# VISUB_V1.net
KiCad netlist of a schematic drawn in EAGLE
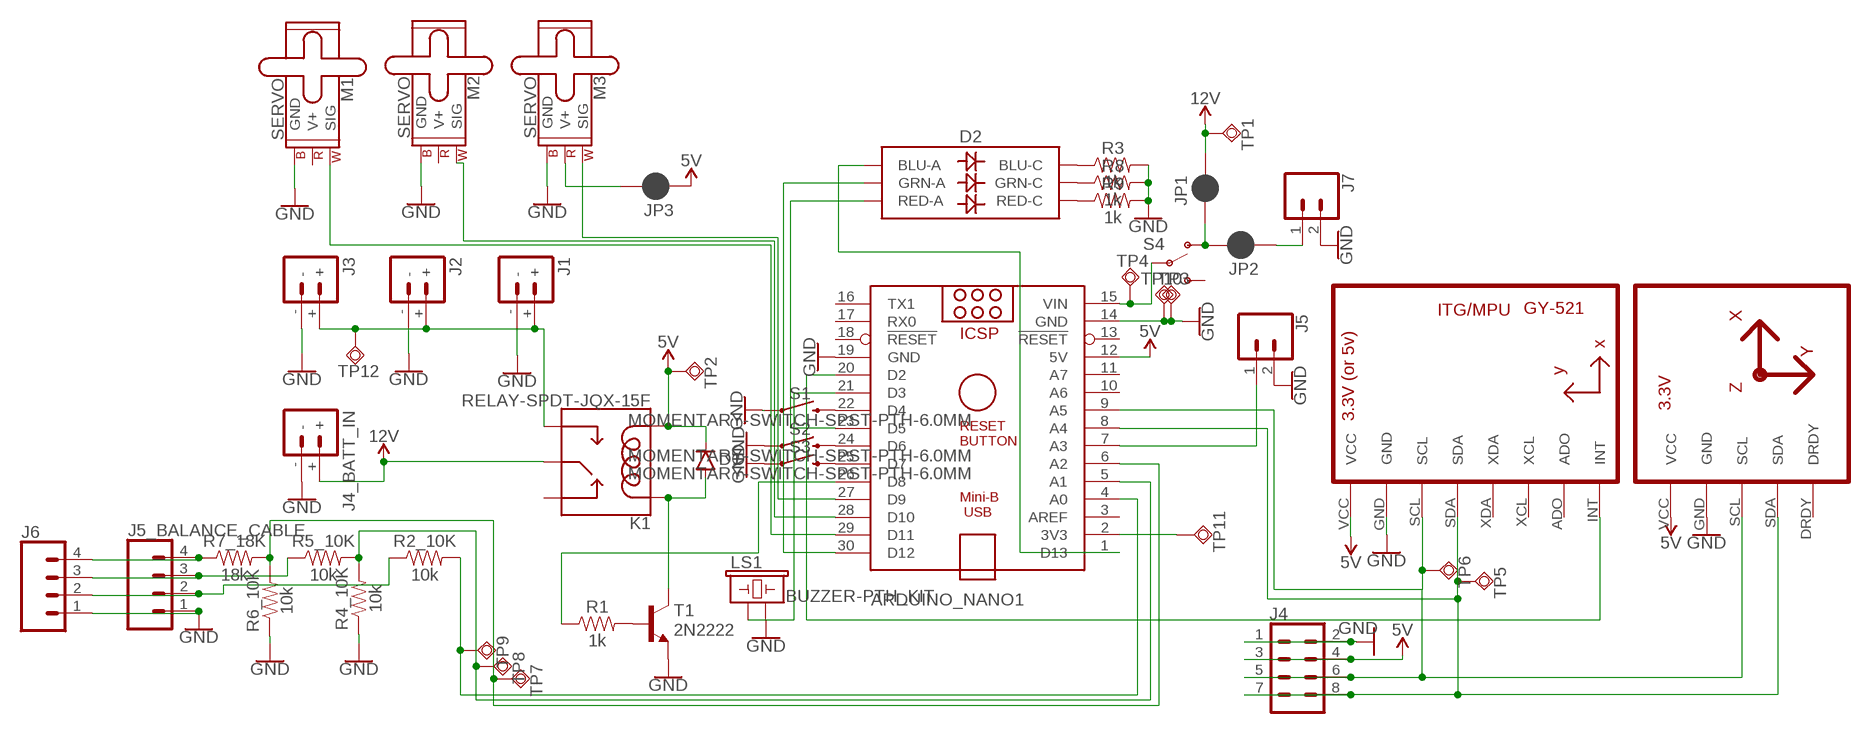
[diagram p0: schematic, sheet 1]

(export (version "E")
  (design (tool "Eeschema 10.0.6"))
  (components
    (comp (ref "ARDUINO_NANO1")
      (value "ARDUINO_NANO")
      (footprint "eagle-import:ARDUINO_NANO")
      (libsource (lib "eagle-import") (part "ARDUINO_NANO"))
    )
    (comp (ref "D1")
      (value "DIODE1N4148")
      (footprint "eagle-import:DIODE-1N4148")
      (libsource (lib "eagle-import") (part "DIODE1N4148"))
    )
    (comp (ref "D2")
      (value "LED-RGBNO_IC")
      (footprint "eagle-import:LED-TRICOLOR-5050")
      (libsource (lib "eagle-import") (part "LED-RGBNO_IC"))
    )
    (comp (ref "J1")
      (value "BATTERY_CONN_DEANS")
      (footprint "eagle-import:DEANS")
      (libsource (lib "eagle-import") (part "BATTERY_CONN_DEANS"))
    )
    (comp (ref "J2")
      (value "BATTERY_CONN_DEANS")
      (footprint "eagle-import:DEANS")
      (libsource (lib "eagle-import") (part "BATTERY_CONN_DEANS"))
    )
    (comp (ref "J3")
      (value "BATTERY_CONN_DEANS")
      (footprint "eagle-import:DEANS")
      (libsource (lib "eagle-import") (part "BATTERY_CONN_DEANS"))
    )
    (comp (ref "J4")
      (value "CONN_04X2")
      (footprint "eagle-import:2X4")
      (libsource (lib "eagle-import") (part "CONN_04X2"))
    )
    (comp (ref "J4_BATT_IN")
      (value "BATTERY_CONN_DEANS")
      (footprint "eagle-import:DEANS")
      (libsource (lib "eagle-import") (part "BATTERY_CONN_DEANS"))
    )
    (comp (ref "J5")
      (value "CONN_02")
      (footprint "eagle-import:1X02")
      (libsource (lib "eagle-import") (part "CONN_02"))
    )
    (comp (ref "J5_BALANCE_CABLE")
      (value "CONN_04POLAR")
      (footprint "eagle-import:MOLEX-1X4")
      (libsource (lib "eagle-import") (part "CONN_04POLAR"))
    )
    (comp (ref "J6")
      (value "CONN_04POLAR")
      (footprint "eagle-import:MOLEX-1X4")
      (libsource (lib "eagle-import") (part "CONN_04POLAR"))
    )
    (comp (ref "J7")
      (value "CONN_02")
      (footprint "eagle-import:1X02")
      (libsource (lib "eagle-import") (part "CONN_02"))
    )
    (comp (ref "JP1")
      (value "JUMPER-SMT_2_NC_PASTE_SILK")
      (footprint "eagle-import:SMT-JUMPER_2_NC_PASTE_SILK")
      (libsource (lib "eagle-import") (part "JUMPER-SMT_2_NC_PASTE_SILK"))
    )
    (comp (ref "JP2")
      (value "JUMPER-SMT_2_NC_PASTE_SILK")
      (footprint "eagle-import:SMT-JUMPER_2_NC_PASTE_SILK")
      (libsource (lib "eagle-import") (part "JUMPER-SMT_2_NC_PASTE_SILK"))
    )
    (comp (ref "JP3")
      (value "JUMPER-SMT_2_NC_PASTE_SILK")
      (footprint "eagle-import:SMT-JUMPER_2_NC_PASTE_SILK")
      (libsource (lib "eagle-import") (part "JUMPER-SMT_2_NC_PASTE_SILK"))
    )
    (comp (ref "K1")
      (value "RELAY-SPDT-JQX-15F")
      (footprint "eagle-import:RELAY-T90")
      (libsource (lib "eagle-import") (part "RELAY-SPDT-JQX-15F"))
    )
    (comp (ref "LS1")
      (value "BUZZER-PTH_KIT")
      (footprint "eagle-import:BUZZER-12MM-KIT")
      (libsource (lib "eagle-import") (part "BUZZER-PTH_KIT"))
    )
    (comp (ref "M1")
      (value "SERVO")
      (footprint "eagle-import:1X03")
      (libsource (lib "eagle-import") (part "SERVO"))
    )
    (comp (ref "M2")
      (value "SERVO")
      (footprint "eagle-import:1X03")
      (libsource (lib "eagle-import") (part "SERVO"))
    )
    (comp (ref "M3")
      (value "SERVO")
      (footprint "eagle-import:1X03")
      (libsource (lib "eagle-import") (part "SERVO"))
    )
    (comp (ref "R1")
      (value "1k")
      (footprint "eagle-import:AXIAL-0.3")
      (libsource (lib "eagle-import") (part "1KOHM-HORIZ-1/4W-5%"))
    )
    (comp (ref "R2_10K")
      (value "10k")
      (footprint "eagle-import:AXIAL-0.3")
      (libsource (lib "eagle-import") (part "1KOHM-HORIZ-1/4W-5%"))
    )
    (comp (ref "R3")
      (value "1k")
      (footprint "eagle-import:0603")
      (libsource (lib "eagle-import") (part "1KOHM-0603-1/10W-1%"))
    )
    (comp (ref "R4_10K")
      (value "10k")
      (footprint "eagle-import:AXIAL-0.3")
      (libsource (lib "eagle-import") (part "1KOHM-HORIZ-1/4W-5%"))
    )
    (comp (ref "R5_10K")
      (value "10k")
      (footprint "eagle-import:AXIAL-0.3")
      (libsource (lib "eagle-import") (part "1KOHM-HORIZ-1/4W-5%"))
    )
    (comp (ref "R6_10K")
      (value "10k")
      (footprint "eagle-import:AXIAL-0.3")
      (libsource (lib "eagle-import") (part "1KOHM-HORIZ-1/4W-5%"))
    )
    (comp (ref "R7_18K")
      (value "18k")
      (footprint "eagle-import:AXIAL-0.3")
      (libsource (lib "eagle-import") (part "1KOHM-HORIZ-1/4W-5%"))
    )
    (comp (ref "R8")
      (value "1k")
      (footprint "eagle-import:0603")
      (libsource (lib "eagle-import") (part "1KOHM-0603-1/10W-1%"))
    )
    (comp (ref "R9")
      (value "1k")
      (footprint "eagle-import:0603")
      (libsource (lib "eagle-import") (part "1KOHM-0603-1/10W-1%"))
    )
    (comp (ref "S1")
      (value "MOMENTARY-SWITCH-SPST-PTH-6.0MM")
      (footprint "eagle-import:TACTILE_SWITCH_PTH_6.0MM")
      (libsource (lib "eagle-import") (part "MOMENTARY-SWITCH-SPST-PTH-6.0MM"))
    )
    (comp (ref "S2")
      (value "MOMENTARY-SWITCH-SPST-PTH-6.0MM")
      (footprint "eagle-import:TACTILE_SWITCH_PTH_6.0MM")
      (libsource (lib "eagle-import") (part "MOMENTARY-SWITCH-SPST-PTH-6.0MM"))
    )
    (comp (ref "S3")
      (value "MOMENTARY-SWITCH-SPST-PTH-6.0MM")
      (footprint "eagle-import:TACTILE_SWITCH_PTH_6.0MM")
      (libsource (lib "eagle-import") (part "MOMENTARY-SWITCH-SPST-PTH-6.0MM"))
    )
    (comp (ref "S4")
      (value "SWITCH-SPDT-PTH-11.6X4.0MM-LOCK")
      (footprint "eagle-import:SWITCH_SPDT_PTH_11.6X4.0MM_LOCK")
      (libsource (lib "eagle-import") (part "SWITCH-SPDT-PTH-11.6X4.0MM-LOCK"))
    )
    (comp (ref "T1")
      (value "2N2222")
      (footprint "eagle-import:TO92-EBC-OVAL")
      (libsource (lib "eagle-import") (part "2N2222"))
    )
    (comp (ref "TP1")
      (value "TESTPAD_TPSQB2,54")
      (footprint "eagle-import:TESTPAD_B2,54")
      (libsource (lib "eagle-import") (part "TESTPAD_TPSQB2,54"))
    )
    (comp (ref "TP2")
      (value "TESTPAD_TPSQB2,54")
      (footprint "eagle-import:TESTPAD_B2,54")
      (libsource (lib "eagle-import") (part "TESTPAD_TPSQB2,54"))
    )
    (comp (ref "TP3")
      (value "TESTPAD_TPSQB2,54")
      (footprint "eagle-import:TESTPAD_B2,54")
      (libsource (lib "eagle-import") (part "TESTPAD_TPSQB2,54"))
    )
    (comp (ref "TP4")
      (value "TESTPAD_TPSQB2,54")
      (footprint "eagle-import:TESTPAD_B2,54")
      (libsource (lib "eagle-import") (part "TESTPAD_TPSQB2,54"))
    )
    (comp (ref "TP5")
      (value "TESTPAD_TPSQB2,54")
      (footprint "eagle-import:TESTPAD_B2,54")
      (libsource (lib "eagle-import") (part "TESTPAD_TPSQB2,54"))
    )
    (comp (ref "TP6")
      (value "TESTPAD_TPSQB2,54")
      (footprint "eagle-import:TESTPAD_B2,54")
      (libsource (lib "eagle-import") (part "TESTPAD_TPSQB2,54"))
    )
    (comp (ref "TP7")
      (value "TESTPAD_TPSQB2,54")
      (footprint "eagle-import:TESTPAD_B2,54")
      (libsource (lib "eagle-import") (part "TESTPAD_TPSQB2,54"))
    )
    (comp (ref "TP8")
      (value "TESTPAD_TPSQB2,54")
      (footprint "eagle-import:TESTPAD_B2,54")
      (libsource (lib "eagle-import") (part "TESTPAD_TPSQB2,54"))
    )
    (comp (ref "TP9")
      (value "TESTPAD_TPSQB2,54")
      (footprint "eagle-import:TESTPAD_B2,54")
      (libsource (lib "eagle-import") (part "TESTPAD_TPSQB2,54"))
    )
    (comp (ref "TP10")
      (value "TESTPAD_TPSQB2,54")
      (footprint "eagle-import:TESTPAD_B2,54")
      (libsource (lib "eagle-import") (part "TESTPAD_TPSQB2,54"))
    )
    (comp (ref "TP11")
      (value "TESTPAD_TPSQB2,54")
      (footprint "eagle-import:TESTPAD_B2,54")
      (libsource (lib "eagle-import") (part "TESTPAD_TPSQB2,54"))
    )
    (comp (ref "TP12")
      (value "TESTPAD_TPSQB2,54")
      (footprint "eagle-import:TESTPAD_B2,54")
      (libsource (lib "eagle-import") (part "TESTPAD_TPSQB2,54"))
    )
    (comp (ref "U1")
      (value "GY-521MPU6050")
      (footprint "eagle-import:GY-521")
      (libsource (lib "eagle-import") (part "GY-521MPU6050"))
    )
    (comp (ref "U2")
      (value "HMC5883LGY-271")
      (footprint "eagle-import:GY-271")
      (libsource (lib "eagle-import") (part "HMC5883LGY-271"))
    )
  )
  (nets
    (net (code "1") (name "5V") (class "Default")
      (node (ref "ARDUINO_NANO1") (pin "12") (pinfunction "5V_12") (pintype "power_in"))
      (node (ref "D1") (pin "C") (pinfunction "C_C") (pintype "passive"))
      (node (ref "J4") (pin "3") (pinfunction "3_3") (pintype "passive"))
      (node (ref "J4") (pin "4") (pinfunction "4_4") (pintype "passive"))
      (node (ref "JP3") (pin "1") (pinfunction "1_1") (pintype "passive"))
      (node (ref "K1") (pin "COIL2") (pinfunction "COIL2_COIL2") (pintype "bidirectional"))
      (node (ref "TP2") (pin "TP") (pinfunction "TP_TP") (pintype "input"))
      (node (ref "U1") (pin "VCC") (pinfunction "VCC_VCC") (pintype "bidirectional"))
      (node (ref "U2") (pin "VCC") (pinfunction "VCC_VCC") (pintype "bidirectional"))
    )
    (net (code "2") (name "12V") (class "Default")
      (node (ref "J4_BATT_IN") (pin "+") (pinfunction "+_+") (pintype "passive"))
      (node (ref "JP1") (pin "2") (pinfunction "2_2") (pintype "passive"))
      (node (ref "K1") (pin "MAIN") (pinfunction "MAIN_MAIN") (pintype "bidirectional"))
      (node (ref "TP1") (pin "TP") (pinfunction "TP_TP") (pintype "input"))
    )
    (net (code "3") (name "GND") (class "Default")
      (node (ref "ARDUINO_NANO1") (pin "14") (pinfunction "GND_14") (pintype "power_in"))
      (node (ref "ARDUINO_NANO1") (pin "19") (pinfunction "GND_19") (pintype "power_in"))
      (node (ref "J1") (pin "-") (pinfunction "-_-") (pintype "passive"))
      (node (ref "J2") (pin "-") (pinfunction "-_-") (pintype "passive"))
      (node (ref "J3") (pin "-") (pinfunction "-_-") (pintype "passive"))
      (node (ref "J4") (pin "1") (pinfunction "1_1") (pintype "passive"))
      (node (ref "J4") (pin "2") (pinfunction "2_2") (pintype "passive"))
      (node (ref "J4_BATT_IN") (pin "-") (pinfunction "-_-") (pintype "passive"))
      (node (ref "J5") (pin "2") (pinfunction "2_2") (pintype "passive"))
      (node (ref "J5_BALANCE_CABLE") (pin "1") (pinfunction "1_1") (pintype "passive"))
      (node (ref "J6") (pin "1") (pinfunction "1_1") (pintype "passive"))
      (node (ref "J7") (pin "2") (pinfunction "2_2") (pintype "passive"))
      (node (ref "LS1") (pin "-") (pinfunction "2_-") (pintype "passive"))
      (node (ref "M1") (pin "3") (pinfunction "GND_3") (pintype "bidirectional"))
      (node (ref "M2") (pin "3") (pinfunction "GND_3") (pintype "bidirectional"))
      (node (ref "M3") (pin "3") (pinfunction "GND_3") (pintype "bidirectional"))
      (node (ref "R3") (pin "2") (pinfunction "2_2") (pintype "passive"))
      (node (ref "R4_10K") (pin "P$1") (pinfunction "1_P$1") (pintype "passive"))
      (node (ref "R6_10K") (pin "P$1") (pinfunction "1_P$1") (pintype "passive"))
      (node (ref "R8") (pin "2") (pinfunction "2_2") (pintype "passive"))
      (node (ref "R9") (pin "2") (pinfunction "2_2") (pintype "passive"))
      (node (ref "S1") (pin "1") (pinfunction "1_1") (pintype "passive"))
      (node (ref "S2") (pin "1") (pinfunction "1_1") (pintype "passive"))
      (node (ref "S3") (pin "1") (pinfunction "1_1") (pintype "passive"))
      (node (ref "T1") (pin "E") (pinfunction "E_E") (pintype "passive"))
      (node (ref "TP10") (pin "TP") (pinfunction "TP_TP") (pintype "input"))
      (node (ref "TP3") (pin "TP") (pinfunction "TP_TP") (pintype "input"))
      (node (ref "U1") (pin "GND") (pinfunction "GND_GND") (pintype "bidirectional"))
      (node (ref "U2") (pin "GND") (pinfunction "GND_GND") (pintype "bidirectional"))
    )
    (net (code "4") (name "Net-(ARDUINO_NANO1-3V3)") (class "Default")
      (node (ref "ARDUINO_NANO1") (pin "2") (pinfunction "3V3_2") (pintype "output"))
      (node (ref "TP11") (pin "TP") (pinfunction "TP_TP") (pintype "input"))
    )
    (net (code "5") (name "Net-(ARDUINO_NANO1-A0)") (class "Default")
      (node (ref "ARDUINO_NANO1") (pin "4") (pinfunction "A0_4") (pintype "bidirectional"))
      (node (ref "R2_10K") (pin "P$2") (pinfunction "2_P$2") (pintype "passive"))
      (node (ref "TP9") (pin "TP") (pinfunction "TP_TP") (pintype "input"))
    )
    (net (code "6") (name "Net-(ARDUINO_NANO1-A1)") (class "Default")
      (node (ref "ARDUINO_NANO1") (pin "5") (pinfunction "A1_5") (pintype "bidirectional"))
      (node (ref "R4_10K") (pin "P$2") (pinfunction "2_P$2") (pintype "passive"))
      (node (ref "R5_10K") (pin "P$2") (pinfunction "2_P$2") (pintype "passive"))
      (node (ref "TP8") (pin "TP") (pinfunction "TP_TP") (pintype "input"))
    )
    (net (code "7") (name "Net-(ARDUINO_NANO1-A2)") (class "Default")
      (node (ref "ARDUINO_NANO1") (pin "6") (pinfunction "A2_6") (pintype "bidirectional"))
      (node (ref "R6_10K") (pin "P$2") (pinfunction "2_P$2") (pintype "passive"))
      (node (ref "R7_18K") (pin "P$2") (pinfunction "2_P$2") (pintype "passive"))
      (node (ref "TP7") (pin "TP") (pinfunction "TP_TP") (pintype "input"))
    )
    (net (code "8") (name "Net-(ARDUINO_NANO1-A3)") (class "Default")
      (node (ref "ARDUINO_NANO1") (pin "7") (pinfunction "A3_7") (pintype "bidirectional"))
      (node (ref "J5") (pin "1") (pinfunction "1_1") (pintype "passive"))
    )
    (net (code "9") (name "Net-(ARDUINO_NANO1-A4)") (class "Default")
      (node (ref "ARDUINO_NANO1") (pin "8") (pinfunction "A4_8") (pintype "bidirectional"))
      (node (ref "J4") (pin "7") (pinfunction "7_7") (pintype "passive"))
      (node (ref "J4") (pin "8") (pinfunction "8_8") (pintype "passive"))
      (node (ref "TP5") (pin "TP") (pinfunction "TP_TP") (pintype "input"))
      (node (ref "U1") (pin "SDA") (pinfunction "SDA_SDA") (pintype "bidirectional"))
      (node (ref "U2") (pin "SDA") (pinfunction "SDA_SDA") (pintype "bidirectional"))
    )
    (net (code "10") (name "Net-(ARDUINO_NANO1-A5)") (class "Default")
      (node (ref "ARDUINO_NANO1") (pin "9") (pinfunction "A5_9") (pintype "bidirectional"))
      (node (ref "J4") (pin "5") (pinfunction "5_5") (pintype "passive"))
      (node (ref "J4") (pin "6") (pinfunction "6_6") (pintype "passive"))
      (node (ref "TP6") (pin "TP") (pinfunction "TP_TP") (pintype "input"))
      (node (ref "U1") (pin "SCL") (pinfunction "SCL_SCL") (pintype "bidirectional"))
      (node (ref "U2") (pin "SCL") (pinfunction "SCL_SCL") (pintype "bidirectional"))
    )
    (net (code "11") (name "Net-(ARDUINO_NANO1-D2)") (class "Default")
      (node (ref "ARDUINO_NANO1") (pin "20") (pinfunction "D2_20") (pintype "bidirectional"))
      (node (ref "U1") (pin "INT") (pinfunction "INT_INT") (pintype "bidirectional"))
    )
    (net (code "12") (name "Net-(ARDUINO_NANO1-D3)") (class "Default")
      (node (ref "ARDUINO_NANO1") (pin "21") (pinfunction "D3_21") (pintype "bidirectional"))
      (node (ref "LS1") (pin "+") (pinfunction "1_+") (pintype "passive"))
    )
    (net (code "13") (name "Net-(ARDUINO_NANO1-D4)") (class "Default")
      (node (ref "ARDUINO_NANO1") (pin "22") (pinfunction "D4_22") (pintype "bidirectional"))
      (node (ref "S1") (pin "3") (pinfunction "2_3") (pintype "passive"))
    )
    (net (code "14") (name "Net-(ARDUINO_NANO1-D5)") (class "Default")
      (node (ref "ARDUINO_NANO1") (pin "23") (pinfunction "D5_23") (pintype "bidirectional"))
      (node (ref "D2") (pin "2") (pinfunction "RED-A_2") (pintype "bidirectional"))
    )
    (net (code "15") (name "Net-(ARDUINO_NANO1-D6)") (class "Default")
      (node (ref "ARDUINO_NANO1") (pin "24") (pinfunction "D6_24") (pintype "bidirectional"))
      (node (ref "S2") (pin "3") (pinfunction "2_3") (pintype "passive"))
    )
    (net (code "16") (name "Net-(ARDUINO_NANO1-D7)") (class "Default")
      (node (ref "ARDUINO_NANO1") (pin "25") (pinfunction "D7_25") (pintype "bidirectional"))
      (node (ref "S3") (pin "3") (pinfunction "2_3") (pintype "passive"))
    )
    (net (code "17") (name "Net-(ARDUINO_NANO1-D8)") (class "Default")
      (node (ref "ARDUINO_NANO1") (pin "26") (pinfunction "D8_26") (pintype "bidirectional"))
      (node (ref "R1") (pin "P$1") (pinfunction "1_P$1") (pintype "passive"))
    )
    (net (code "18") (name "Net-(ARDUINO_NANO1-D9)") (class "Default")
      (node (ref "ARDUINO_NANO1") (pin "27") (pinfunction "D9_27") (pintype "bidirectional"))
      (node (ref "M3") (pin "1") (pinfunction "SIG_1") (pintype "bidirectional"))
    )
    (net (code "19") (name "Net-(ARDUINO_NANO1-D10)") (class "Default")
      (node (ref "ARDUINO_NANO1") (pin "28") (pinfunction "D10_28") (pintype "bidirectional"))
      (node (ref "M2") (pin "1") (pinfunction "SIG_1") (pintype "bidirectional"))
    )
    (net (code "20") (name "Net-(ARDUINO_NANO1-D11)") (class "Default")
      (node (ref "ARDUINO_NANO1") (pin "29") (pinfunction "D11_29") (pintype "bidirectional"))
      (node (ref "M1") (pin "1") (pinfunction "SIG_1") (pintype "bidirectional"))
    )
    (net (code "21") (name "Net-(ARDUINO_NANO1-D12)") (class "Default")
      (node (ref "ARDUINO_NANO1") (pin "30") (pinfunction "D12_30") (pintype "bidirectional"))
      (node (ref "D2") (pin "1") (pinfunction "GRN-A_1") (pintype "bidirectional"))
    )
    (net (code "22") (name "Net-(ARDUINO_NANO1-D13)") (class "Default")
      (node (ref "ARDUINO_NANO1") (pin "1") (pinfunction "D13_1") (pintype "bidirectional"))
      (node (ref "D2") (pin "3") (pinfunction "BLU-A_3") (pintype "bidirectional"))
    )
    (net (code "23") (name "Net-(ARDUINO_NANO1-VIN)") (class "Default")
      (node (ref "ARDUINO_NANO1") (pin "15") (pinfunction "VIN_15") (pintype "power_in"))
      (node (ref "S4") (pin "2") (pinfunction "P_2") (pintype "passive"))
      (node (ref "TP4") (pin "TP") (pinfunction "TP_TP") (pintype "input"))
    )
    (net (code "24") (name "Net-(D1-PadA)") (class "Default")
      (node (ref "D1") (pin "A") (pinfunction "A_A") (pintype "passive"))
      (node (ref "K1") (pin "COIL1") (pinfunction "COIL1_COIL1") (pintype "bidirectional"))
      (node (ref "T1") (pin "C") (pinfunction "C_C") (pintype "passive"))
    )
    (net (code "25") (name "Net-(D2-BLU-C)") (class "Default")
      (node (ref "D2") (pin "4") (pinfunction "BLU-C_4") (pintype "bidirectional"))
      (node (ref "R3") (pin "1") (pinfunction "1_1") (pintype "passive"))
    )
    (net (code "26") (name "Net-(D2-GRN-C)") (class "Default")
      (node (ref "D2") (pin "6") (pinfunction "GRN-C_6") (pintype "bidirectional"))
      (node (ref "R8") (pin "1") (pinfunction "1_1") (pintype "passive"))
    )
    (net (code "27") (name "Net-(D2-RED-C)") (class "Default")
      (node (ref "D2") (pin "5") (pinfunction "RED-C_5") (pintype "bidirectional"))
      (node (ref "R9") (pin "1") (pinfunction "1_1") (pintype "passive"))
    )
    (net (code "28") (name "Net-(J1-Pad+)") (class "Default")
      (node (ref "J1") (pin "+") (pinfunction "+_+") (pintype "passive"))
      (node (ref "J2") (pin "+") (pinfunction "+_+") (pintype "passive"))
      (node (ref "J3") (pin "+") (pinfunction "+_+") (pintype "passive"))
      (node (ref "K1") (pin "NO") (pinfunction "NO_NO") (pintype "bidirectional"))
      (node (ref "TP12") (pin "TP") (pinfunction "TP_TP") (pintype "input"))
    )
    (net (code "29") (name "Net-(J7-Pad1)") (class "Default")
      (node (ref "J7") (pin "1") (pinfunction "1_1") (pintype "passive"))
      (node (ref "JP2") (pin "1") (pinfunction "1_1") (pintype "passive"))
    )
    (net (code "30") (name "Net-(M3-V+)") (class "Default")
      (node (ref "JP3") (pin "2") (pinfunction "2_2") (pintype "passive"))
      (node (ref "M3") (pin "2") (pinfunction "V+_2") (pintype "bidirectional"))
    )
    (net (code "31") (name "Net-(R1-2)") (class "Default")
      (node (ref "R1") (pin "P$2") (pinfunction "2_P$2") (pintype "passive"))
      (node (ref "T1") (pin "B") (pinfunction "B_B") (pintype "passive"))
    )
    (net (code "32") (name "Net-(R2_10K-1)") (class "Default")
      (node (ref "J5_BALANCE_CABLE") (pin "2") (pinfunction "2_2") (pintype "passive"))
      (node (ref "J6") (pin "2") (pinfunction "2_2") (pintype "passive"))
      (node (ref "R2_10K") (pin "P$1") (pinfunction "1_P$1") (pintype "passive"))
    )
    (net (code "33") (name "Net-(R5_10K-1)") (class "Default")
      (node (ref "J5_BALANCE_CABLE") (pin "3") (pinfunction "3_3") (pintype "passive"))
      (node (ref "J6") (pin "3") (pinfunction "3_3") (pintype "passive"))
      (node (ref "R5_10K") (pin "P$1") (pinfunction "1_P$1") (pintype "passive"))
    )
    (net (code "34") (name "Net-(R7_18K-1)") (class "Default")
      (node (ref "J5_BALANCE_CABLE") (pin "4") (pinfunction "4_4") (pintype "passive"))
      (node (ref "J6") (pin "4") (pinfunction "4_4") (pintype "passive"))
      (node (ref "R7_18K") (pin "P$1") (pinfunction "1_P$1") (pintype "passive"))
    )
    (net (code "35") (name "Net-(S4-O)") (class "Default")
      (node (ref "JP1") (pin "1") (pinfunction "1_1") (pintype "passive"))
      (node (ref "JP2") (pin "2") (pinfunction "2_2") (pintype "passive"))
      (node (ref "S4") (pin "1") (pinfunction "O_1") (pintype "passive"))
    )
    (net (code "36") (name "unconnected-(ARDUINO_NANO1-A6-Pad10)") (class "Default")
      (node (ref "ARDUINO_NANO1") (pin "10") (pinfunction "A6_10") (pintype "bidirectional"))
    )
    (net (code "37") (name "unconnected-(ARDUINO_NANO1-A7-Pad11)") (class "Default")
      (node (ref "ARDUINO_NANO1") (pin "11") (pinfunction "A7_11") (pintype "bidirectional"))
    )
    (net (code "38") (name "unconnected-(ARDUINO_NANO1-AREF-Pad3)") (class "Default")
      (node (ref "ARDUINO_NANO1") (pin "3") (pinfunction "AREF_3") (pintype "input"))
    )
    (net (code "39") (name "unconnected-(ARDUINO_NANO1-RX0-Pad17)") (class "Default")
      (node (ref "ARDUINO_NANO1") (pin "17") (pinfunction "RX0_17") (pintype "bidirectional"))
    )
    (net (code "40") (name "unconnected-(ARDUINO_NANO1-TX1-Pad16)") (class "Default")
      (node (ref "ARDUINO_NANO1") (pin "16") (pinfunction "TX1_16") (pintype "bidirectional"))
    )
    (net (code "41") (name "unconnected-(ARDUINO_NANO1-~{RESET}-Pad13)") (class "Default")
      (node (ref "ARDUINO_NANO1") (pin "13") (pinfunction "~{RESET}_13") (pintype "input"))
    )
    (net (code "42") (name "unconnected-(ARDUINO_NANO1-~{RESET}-Pad18)") (class "Default")
      (node (ref "ARDUINO_NANO1") (pin "18") (pinfunction "~{RESET}_18") (pintype "input"))
    )
    (net (code "43") (name "unconnected-(K1-PadNC)") (class "Default")
      (node (ref "K1") (pin "NC") (pinfunction "NC_NC") (pintype "bidirectional"))
    )
    (net (code "44") (name "unconnected-(M1-V+-Pad2)") (class "Default")
      (node (ref "M1") (pin "2") (pinfunction "V+_2") (pintype "bidirectional"))
    )
    (net (code "45") (name "unconnected-(M2-V+-Pad2)") (class "Default")
      (node (ref "M2") (pin "2") (pinfunction "V+_2") (pintype "bidirectional"))
    )
    (net (code "46") (name "unconnected-(S4-S-Pad3)") (class "Default")
      (node (ref "S4") (pin "3") (pinfunction "S_3") (pintype "passive"))
    )
    (net (code "47") (name "unconnected-(U1-PadADO)") (class "Default")
      (node (ref "U1") (pin "ADO") (pinfunction "ADO_ADO") (pintype "bidirectional"))
    )
    (net (code "48") (name "unconnected-(U1-PadXCL)") (class "Default")
      (node (ref "U1") (pin "XCL") (pinfunction "XCL_XCL") (pintype "bidirectional"))
    )
    (net (code "49") (name "unconnected-(U1-PadXDA)") (class "Default")
      (node (ref "U1") (pin "XDA") (pinfunction "XDA_XDA") (pintype "bidirectional"))
    )
    (net (code "50") (name "unconnected-(U2-PadDRDY)") (class "Default")
      (node (ref "U2") (pin "DRDY") (pinfunction "DRDY_DRDY") (pintype "bidirectional"))
    )
  )
)
